# CPU.net
KiCad netlist of a schematic drawn in Altium Designer
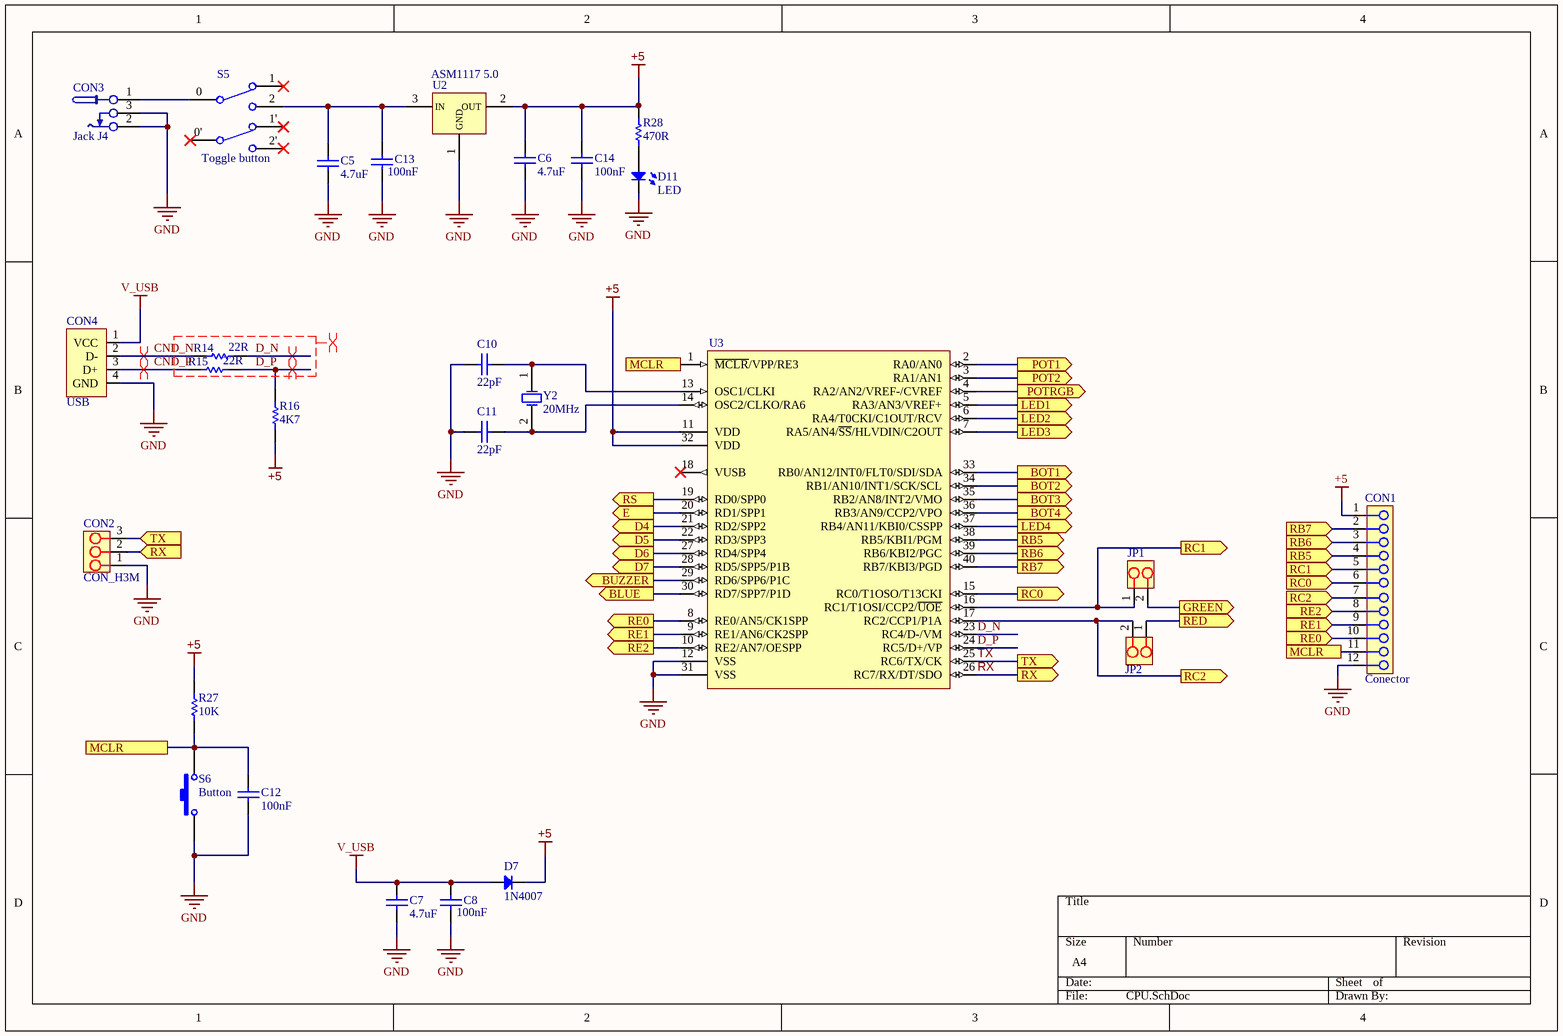
[diagram p0: CPU.SchDoc]

(export (version "E")
  (design (tool "Eeschema 10.0.6"))
  (components
    (comp (ref "C5")
      (value "4.7uF")
      (footprint "CAP_ELEC_1206")
      (description "Capacitor Cerâmico SMD X7R 50V - 1206")
      (libsource (lib "HEIMDALL-DEVPICKIT-V2.1") (part "SMD Eletrolitic Capacitor"))
    )
    (comp (ref "C6")
      (value "4.7uF")
      (footprint "CAP_ELEC_1206")
      (description "Capacitor Cerâmico SMD X7R 50V - 1206")
      (libsource (lib "HEIMDALL-DEVPICKIT-V2.1") (part "SMD Eletrolitic Capacitor"))
    )
    (comp (ref "C7")
      (value "4.7uF")
      (footprint "CC1206")
      (description "Capacitor ceramica X7R 50V 1206")
      (libsource (lib "passivos_smd") (part "CC1206"))
    )
    (comp (ref "C8")
      (value "100nF")
      (footprint "SMD Capacitor")
      (description "Multilayer Ceramic\r\nCapacitor 0805")
      (libsource (lib "Aken") (part "SMD Capacitor"))
    )
    (comp (ref "C10")
      (value "22pF")
      (footprint "SMD Capacitor")
      (description "Multilayer Ceramic\r\nCapacitor 0805")
      (libsource (lib "Aken") (part "SMD Capacitor"))
    )
    (comp (ref "C11")
      (value "22pF")
      (footprint "SMD Capacitor")
      (description "Multilayer Ceramic\r\nCapacitor 0805")
      (libsource (lib "Aken") (part "SMD Capacitor"))
    )
    (comp (ref "C12")
      (value "100nF")
      (footprint "SMD Capacitor")
      (description "Multilayer Ceramic\r\nCapacitor 0805")
      (libsource (lib "Aken") (part "SMD Capacitor"))
    )
    (comp (ref "C13")
      (value "100nF")
      (footprint "SMD Capacitor")
      (description "Multilayer Ceramic\r\nCapacitor 0805")
      (libsource (lib "Aken") (part "SMD Capacitor"))
    )
    (comp (ref "C14")
      (value "100nF")
      (footprint "SMD Capacitor")
      (description "Multilayer Ceramic\r\nCapacitor 0805")
      (libsource (lib "Aken") (part "SMD Capacitor"))
    )
    (comp (ref "CON1") (value "Conector") (footprint "CON_6x2_M") (libsource (lib "Aken") (part "CON_6x2_M")))
    (comp (ref "CON2")
      (value "CON_H3M")
      (footprint "CON_3P_M")
      (description "Molex M 3T")
      (libsource (lib "Aken") (part "CON_H3M"))
    )
    (comp (ref "CON3")
      (value "Jack J4")
      (footprint "J4")
      (description "Conector DC Power Jack J4 2.5mm")
      (fields (field (name "MANUFACTURER") "CUI") (field (name "MANUFACTURER PART NUMBER") "PJ-102BH"))
      (libsource (lib "Adono_Library2") (part "CON-J4"))
    )
    (comp (ref "CON4")
      (value "USB")
      (footprint "USB_SMD")
      (description "Porta USB \r\ntipo B femea")
      (libsource (lib "HEIMDALL-DEVPICKIT-V2.1") (part "Porta_USB_B"))
    )
    (comp (ref "D7")
      (value "1N4007")
      (footprint "SMA")
      (description "1N4007-SMD")
      (libsource (lib "ativos_smd") (part "M7"))
    )
    (comp (ref "D11")
      (value "LED")
      (footprint "LED_GREEN")
      (description "Light Emissor Diode - 5mm")
      (fields
        (field (name "MANUFACTURER") "Kingbright")
        (field (name "MANUFACTURER PART NUMBER") "WP7113LGD")
      )
      (libsource (lib "Adono_Library2") (part "LED-GREEN"))
    )
    (comp (ref "JP1")
      (value "CON_H2M")
      (footprint "Header2-M")
      (description "Molex M 2T")
      (fields (field (name "MANUFACTURER") "Harwin") (field (name "MANUFACTURER PART NUMBER") "M20-9990246"))
      (libsource (lib "Adono_Library") (part "CON_H2M"))
    )
    (comp (ref "JP2")
      (value "CON_H2M")
      (footprint "Header2-M")
      (description "Molex M 2T")
      (fields (field (name "MANUFACTURER") "Harwin") (field (name "MANUFACTURER PART NUMBER") "M20-9990246"))
      (libsource (lib "") (part "CON_H2M_1"))
    )
    (comp (ref "R14")
      (value "22R")
      (footprint "SMD Resistor")
      (description "SMD Resistor  MCU 0805")
      (libsource (lib "HEIMDALL-DEVPICKIT-V2.1") (part "SMD Resistor"))
    )
    (comp (ref "R15")
      (value "22R")
      (footprint "SMD Resistor")
      (description "SMD Resistor  MCU 0805")
      (libsource (lib "HEIMDALL-DEVPICKIT-V2.1") (part "SMD Resistor"))
    )
    (comp (ref "R16")
      (value "4K7")
      (footprint "SMD Resistor")
      (description "SMD Resistor  MCU 0805")
      (libsource (lib "HEIMDALL-DEVPICKIT-V2.1") (part "SMD Resistor"))
    )
    (comp (ref "R27")
      (value "10K")
      (footprint "SMD Resistor")
      (description "SMD Resistor  MCU 0805")
      (libsource (lib "Aken") (part "SMD Resistor"))
    )
    (comp (ref "R28")
      (value "470R")
      (footprint "SMD Resistor")
      (description "SMD Resistor  MCU 0805")
      (libsource (lib "Aken") (part "SMD Resistor"))
    )
    (comp (ref "S5")
      (value "Toggle button")
      (footprint "Toggle button")
      (libsource (lib "Aken") (part "Toggle button"))
    )
    (comp (ref "S6")
      (value "Button")
      (footprint "BUTTON")
      (description "Tactil Switch")
      (fields
        (field (name "MANUFACTURER") "Panasonic")
        (field (name "MANUFACTURER PART NUMBER") "EVQ-PAC07K")
      )
      (libsource (lib "Adono_Library2") (part "Button"))
    )
    (comp (ref "U2")
      (value "ASM1117 5.0")
      (footprint "ASM1117 5.0")
      (description "LOW DROPOUT VOLTAGE REGULATOR")
      (libsource (lib "Aken") (part "ASM1117 5.0"))
    )
    (comp (ref "U3")
      (value "PIC18F4550")
      (footprint "DIP40")
      (fields
        (field (name "MANUFACTURER") "Microchip")
        (field (name "MANUFACTURER PART NUMBER") "PIC18F4550-I/P")
      )
      (libsource (lib "Adono_Library2") (part "PIC18F4550"))
    )
    (comp (ref "Y2")
      (value "20MHz")
      (footprint "CRYSTAL")
      (description "Quartz Crystal")
      (fields
        (field (name "MANUFACTURER") "ECS International")
        (field (name "MANUFACTURER PART NUMBER") "ECS-200-18-4XEN")
      )
      (libsource (lib "Adono_Library") (part "Crystal_Oscillator"))
    )
  )
  (nets
    (net (code "1") (name "+5") (class "Default")
      (node (ref "C14") (pin "2") (pinfunction "2_2") (pintype "passive"))
      (node (ref "C6") (pin "2") (pinfunction "2_2") (pintype "passive"))
      (node (ref "CON1") (pin "1") (pinfunction "1_1") (pintype "passive"))
      (node (ref "D7") (pin "2") (pinfunction "K_2") (pintype "passive"))
      (node (ref "R16") (pin "1") (pinfunction "1_1") (pintype "passive"))
      (node (ref "R27") (pin "2") (pinfunction "2_2") (pintype "passive"))
      (node (ref "R28") (pin "2") (pinfunction "2_2") (pintype "passive"))
      (node (ref "U2") (pin "2") (pinfunction "OUT_2") (pintype "passive"))
      (node (ref "U3") (pin "11") (pinfunction "VDD_11") (pintype "power_in"))
      (node (ref "U3") (pin "32") (pinfunction "VDD_32") (pintype "power_in"))
    )
    (net (code "2") (name "/BLUE") (class "Default")
      (node (ref "U3") (pin "30") (pinfunction "RD7/SPP7/P1D_30") (pintype "bidirectional"))
    )
    (net (code "3") (name "/BOT1") (class "Default")
      (node (ref "U3") (pin "33") (pinfunction "RB0/AN12/INT0/FLT0/SDI/SDA_33") (pintype "bidirectional"))
    )
    (net (code "4") (name "/BOT2") (class "Default")
      (node (ref "U3") (pin "34") (pinfunction "RB1/AN10/INT1/SCK/SCL_34") (pintype "bidirectional"))
    )
    (net (code "5") (name "/BOT3") (class "Default")
      (node (ref "U3") (pin "35") (pinfunction "RB2/AN8/INT2/VMO_35") (pintype "bidirectional"))
    )
    (net (code "6") (name "/BOT4") (class "Default")
      (node (ref "U3") (pin "36") (pinfunction "RB3/AN9/CCP2/VPO_36") (pintype "bidirectional"))
    )
    (net (code "7") (name "/BUZZER") (class "Default")
      (node (ref "U3") (pin "29") (pinfunction "RD6/SPP6/P1C_29") (pintype "bidirectional"))
    )
    (net (code "8") (name "/CND_N") (class "Default")
      (node (ref "CON4") (pin "2") (pinfunction "D-_2") (pintype "passive"))
      (node (ref "R14") (pin "1") (pinfunction "1_1") (pintype "passive"))
    )
    (net (code "9") (name "/CND_P") (class "Default")
      (node (ref "CON4") (pin "3") (pinfunction "D+_3") (pintype "passive"))
      (node (ref "R15") (pin "1") (pinfunction "1_1") (pintype "passive"))
    )
    (net (code "10") (name "/D4") (class "Default")
      (node (ref "U3") (pin "21") (pinfunction "RD2/SPP2_21") (pintype "bidirectional"))
    )
    (net (code "11") (name "/D5") (class "Default")
      (node (ref "U3") (pin "22") (pinfunction "RD3/SPP3_22") (pintype "bidirectional"))
    )
    (net (code "12") (name "/D6") (class "Default")
      (node (ref "U3") (pin "27") (pinfunction "RD4/SPP4_27") (pintype "bidirectional"))
    )
    (net (code "13") (name "/D7") (class "Default")
      (node (ref "U3") (pin "28") (pinfunction "RD5/SPP5/P1B_28") (pintype "bidirectional"))
    )
    (net (code "14") (name "/D_N") (class "Default")
      (node (ref "R14") (pin "2") (pinfunction "2_2") (pintype "passive"))
      (node (ref "U3") (pin "23") (pinfunction "RC4/D-/VM_23") (pintype "bidirectional"))
    )
    (net (code "15") (name "/D_P") (class "Default")
      (node (ref "R15") (pin "2") (pinfunction "2_2") (pintype "passive"))
      (node (ref "R16") (pin "2") (pinfunction "2_2") (pintype "passive"))
      (node (ref "U3") (pin "24") (pinfunction "RC5/D+/VP_24") (pintype "bidirectional"))
    )
    (net (code "16") (name "/E") (class "Default")
      (node (ref "U3") (pin "20") (pinfunction "RD1/SPP1_20") (pintype "bidirectional"))
    )
    (net (code "17") (name "/GREEN") (class "Default")
      (node (ref "JP1") (pin "2") (pinfunction "2_2") (pintype "passive"))
    )
    (net (code "18") (name "/LED1") (class "Default")
      (node (ref "U3") (pin "5") (pinfunction "RA3/AN3/VREF+_5") (pintype "bidirectional"))
    )
    (net (code "19") (name "/LED2") (class "Default")
      (node (ref "U3") (pin "6") (pinfunction "RA4/T0CKI/C1OUT/RCV_6") (pintype "bidirectional"))
    )
    (net (code "20") (name "/LED3") (class "Default")
      (node (ref "U3") (pin "7") (pinfunction "RA5/AN4/~{SS}/HLVDIN/C2OUT_7") (pintype "bidirectional"))
    )
    (net (code "21") (name "/LED4") (class "Default")
      (node (ref "U3") (pin "37") (pinfunction "RB4/AN11/KBI0/CSSPP_37") (pintype "bidirectional"))
    )
    (net (code "22") (name "/MCLR") (class "Default")
      (node (ref "C12") (pin "2") (pinfunction "2_2") (pintype "passive"))
      (node (ref "CON1") (pin "11") (pinfunction "11_11") (pintype "passive"))
      (node (ref "R27") (pin "1") (pinfunction "1_1") (pintype "passive"))
      (node (ref "S6") (pin "2") (pinfunction "2_2") (pintype "passive"))
      (node (ref "U3") (pin "1") (pinfunction "~{MCLR}/VPP/RE3_1") (pintype "input"))
    )
    (net (code "23") (name "/POT1") (class "Default")
      (node (ref "U3") (pin "2") (pinfunction "RA0/AN0_2") (pintype "bidirectional"))
    )
    (net (code "24") (name "/POT2") (class "Default")
      (node (ref "U3") (pin "3") (pinfunction "RA1/AN1_3") (pintype "bidirectional"))
    )
    (net (code "25") (name "/POTRGB") (class "Default")
      (node (ref "U3") (pin "4") (pinfunction "RA2/AN2/VREF-/CVREF_4") (pintype "bidirectional"))
    )
    (net (code "26") (name "/RB5") (class "Default")
      (node (ref "CON1") (pin "4") (pinfunction "4_4") (pintype "passive"))
      (node (ref "U3") (pin "38") (pinfunction "RB5/KBI1/PGM_38") (pintype "bidirectional"))
    )
    (net (code "27") (name "/RB6") (class "Default")
      (node (ref "CON1") (pin "3") (pinfunction "3_3") (pintype "passive"))
      (node (ref "U3") (pin "39") (pinfunction "RB6/KBI2/PGC_39") (pintype "bidirectional"))
    )
    (net (code "28") (name "/RB7") (class "Default")
      (node (ref "CON1") (pin "2") (pinfunction "2_2") (pintype "passive"))
      (node (ref "U3") (pin "40") (pinfunction "RB7/KBI3/PGD_40") (pintype "bidirectional"))
    )
    (net (code "29") (name "/RC0") (class "Default")
      (node (ref "CON1") (pin "6") (pinfunction "6_6") (pintype "passive"))
      (node (ref "U3") (pin "15") (pinfunction "RC0/T1OSO/T13CKI_15") (pintype "bidirectional"))
    )
    (net (code "30") (name "/RC1") (class "Default")
      (node (ref "CON1") (pin "5") (pinfunction "5_5") (pintype "passive"))
      (node (ref "JP1") (pin "1") (pinfunction "1_1") (pintype "passive"))
      (node (ref "U3") (pin "16") (pinfunction "RC1/T1OSI/CCP2/~{UOE}_16") (pintype "bidirectional"))
    )
    (net (code "31") (name "/RC2") (class "Default")
      (node (ref "CON1") (pin "7") (pinfunction "7_7") (pintype "passive"))
      (node (ref "JP2") (pin "2") (pinfunction "2_2") (pintype "passive"))
      (node (ref "U3") (pin "17") (pinfunction "RC2/CCP1/P1A_17") (pintype "bidirectional"))
    )
    (net (code "32") (name "/RE0") (class "Default")
      (node (ref "CON1") (pin "10") (pinfunction "10_10") (pintype "passive"))
      (node (ref "U3") (pin "8") (pinfunction "RE0/AN5/CK1SPP_8") (pintype "bidirectional"))
    )
    (net (code "33") (name "/RE1") (class "Default")
      (node (ref "CON1") (pin "9") (pinfunction "9_9") (pintype "passive"))
      (node (ref "U3") (pin "9") (pinfunction "RE1/AN6/CK2SPP_9") (pintype "bidirectional"))
    )
    (net (code "34") (name "/RE2") (class "Default")
      (node (ref "CON1") (pin "8") (pinfunction "8_8") (pintype "passive"))
      (node (ref "U3") (pin "10") (pinfunction "RE2/AN7/OESPP_10") (pintype "bidirectional"))
    )
    (net (code "35") (name "/RED") (class "Default")
      (node (ref "JP2") (pin "1") (pinfunction "1_1") (pintype "passive"))
    )
    (net (code "36") (name "/RS") (class "Default")
      (node (ref "U3") (pin "19") (pinfunction "RD0/SPP0_19") (pintype "bidirectional"))
    )
    (net (code "37") (name "/RX") (class "Default")
      (node (ref "CON2") (pin "2") (pinfunction "2_2") (pintype "passive"))
      (node (ref "U3") (pin "26") (pinfunction "RC7/RX/DT/SDO_26") (pintype "bidirectional"))
    )
    (net (code "38") (name "/TX") (class "Default")
      (node (ref "CON2") (pin "3") (pinfunction "3_3") (pintype "passive"))
      (node (ref "U3") (pin "25") (pinfunction "RC6/TX/CK_25") (pintype "bidirectional"))
    )
    (net (code "39") (name "GND") (class "Default")
      (node (ref "C10") (pin "1") (pinfunction "1_1") (pintype "passive"))
      (node (ref "C11") (pin "1") (pinfunction "1_1") (pintype "passive"))
      (node (ref "C12") (pin "1") (pinfunction "1_1") (pintype "passive"))
      (node (ref "C13") (pin "1") (pinfunction "1_1") (pintype "passive"))
      (node (ref "C14") (pin "1") (pinfunction "1_1") (pintype "passive"))
      (node (ref "C5") (pin "1") (pinfunction "1_1") (pintype "passive"))
      (node (ref "C6") (pin "1") (pinfunction "1_1") (pintype "passive"))
      (node (ref "C7") (pin "1") (pinfunction "1_1") (pintype "passive"))
      (node (ref "C8") (pin "1") (pinfunction "1_1") (pintype "passive"))
      (node (ref "CON1") (pin "12") (pinfunction "12_12") (pintype "passive"))
      (node (ref "CON2") (pin "1") (pinfunction "1_1") (pintype "passive"))
      (node (ref "CON3") (pin "2") (pinfunction "2_2") (pintype "passive"))
      (node (ref "CON3") (pin "3") (pinfunction "3_3") (pintype "passive"))
      (node (ref "CON4") (pin "4") (pinfunction "GND_4") (pintype "passive"))
      (node (ref "D11") (pin "K") (pinfunction "K_K") (pintype "passive"))
      (node (ref "S6") (pin "1") (pinfunction "1_1") (pintype "passive"))
      (node (ref "U2") (pin "1") (pinfunction "GND_1") (pintype "passive"))
      (node (ref "U3") (pin "12") (pinfunction "VSS_12") (pintype "power_in"))
      (node (ref "U3") (pin "31") (pinfunction "VSS_31") (pintype "power_in"))
    )
    (net (code "40") (name "Net-(CON3-Pad1)") (class "Default")
      (node (ref "CON3") (pin "1") (pinfunction "1_1") (pintype "passive"))
      (node (ref "S5") (pin "0") (pinfunction "0_0") (pintype "passive"))
    )
    (net (code "41") (name "Net-(D11-PadA)") (class "Default")
      (node (ref "D11") (pin "A") (pinfunction "A_A") (pintype "passive"))
      (node (ref "R28") (pin "1") (pinfunction "1_1") (pintype "passive"))
    )
    (net (code "42") (name "Net-(U2-IN)") (class "Default")
      (node (ref "C13") (pin "2") (pinfunction "2_2") (pintype "passive"))
      (node (ref "C5") (pin "2") (pinfunction "2_2") (pintype "passive"))
      (node (ref "S5") (pin "2") (pinfunction "2_2") (pintype "passive"))
      (node (ref "U2") (pin "3") (pinfunction "IN_3") (pintype "passive"))
    )
    (net (code "43") (name "Net-(U3-OSC1{slash}CLKI)") (class "Default")
      (node (ref "C10") (pin "2") (pinfunction "2_2") (pintype "passive"))
      (node (ref "U3") (pin "13") (pinfunction "OSC1/CLKI_13") (pintype "input"))
      (node (ref "Y2") (pin "1") (pinfunction "OSC1_1") (pintype "passive"))
    )
    (net (code "44") (name "Net-(U3-OSC2{slash}CLKO{slash}RA6)") (class "Default")
      (node (ref "C11") (pin "2") (pinfunction "2_2") (pintype "passive"))
      (node (ref "U3") (pin "14") (pinfunction "OSC2/CLKO/RA6_14") (pintype "bidirectional"))
      (node (ref "Y2") (pin "2") (pinfunction "OSC2_2") (pintype "passive"))
    )
    (net (code "45") (name "V_USB") (class "Default")
      (node (ref "C7") (pin "2") (pinfunction "2_2") (pintype "passive"))
      (node (ref "C8") (pin "2") (pinfunction "2_2") (pintype "passive"))
      (node (ref "CON4") (pin "1") (pinfunction "VCC_1") (pintype "passive"))
      (node (ref "D7") (pin "1") (pinfunction "A_1") (pintype "passive"))
    )
    (net (code "46") (name "unconnected-(S5-Pad0')") (class "Default")
      (node (ref "S5") (pin "0'") (pinfunction "0'_0'") (pintype "passive"))
    )
    (net (code "47") (name "unconnected-(S5-Pad1')") (class "Default")
      (node (ref "S5") (pin "1'") (pinfunction "1'_1'") (pintype "passive+no_connect"))
    )
    (net (code "48") (name "unconnected-(S5-Pad1)") (class "Default")
      (node (ref "S5") (pin "1") (pinfunction "1_1") (pintype "passive+no_connect"))
    )
    (net (code "49") (name "unconnected-(S5-Pad2')") (class "Default")
      (node (ref "S5") (pin "2'") (pinfunction "2'_2'") (pintype "passive+no_connect"))
    )
    (net (code "50") (name "unconnected-(U3-VUSB-Pad18)") (class "Default")
      (node (ref "U3") (pin "18") (pinfunction "VUSB_18") (pintype "output+no_connect"))
    )
  )
)
